# RF315.net
KiCad netlist of a schematic drawn in Altium Designer
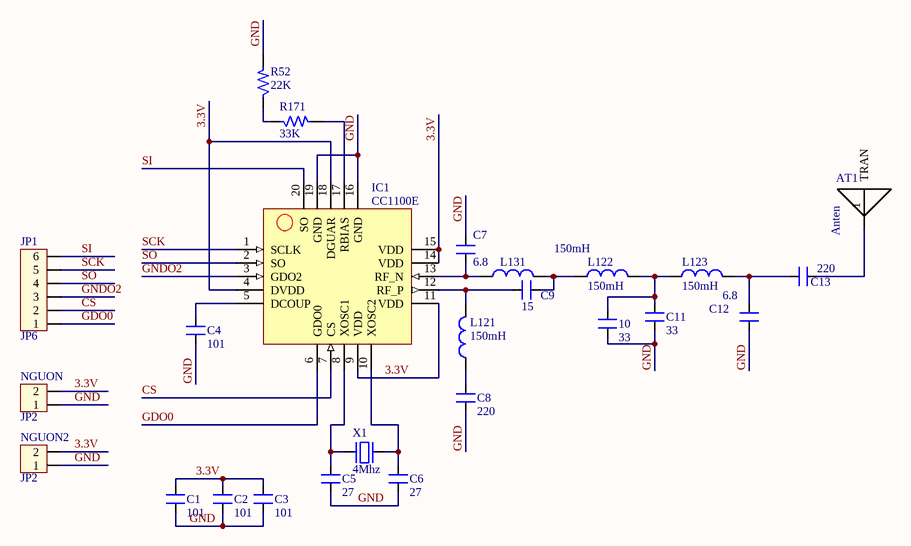
[diagram p0: RF315.SchDoc]

(export (version "E")
  (design (tool "Eeschema 10.0.6"))
  (components
    (comp (ref "10")
      (value "33")
      (footprint "SM-0805")
      (description "Cap SMD")
      (libsource (lib "syhaunguyen") (part "CM"))
    )
    (comp (ref "AT1") (value "Anten") (footprint "VIT") (libsource (lib "Antena") (part "Anten")))
    (comp (ref "C1")
      (value "101")
      (footprint "SM-0805")
      (description "Cap SMD")
      (libsource (lib "syhaunguyen") (part "CM"))
    )
    (comp (ref "C2")
      (value "101")
      (footprint "SM-0805")
      (description "Cap SMD")
      (libsource (lib "syhaunguyen") (part "CM"))
    )
    (comp (ref "C3")
      (value "101")
      (footprint "SM-0805")
      (description "Cap SMD")
      (libsource (lib "syhaunguyen") (part "CM"))
    )
    (comp (ref "C4")
      (value "101")
      (footprint "SM-0805")
      (description "Cap SMD")
      (libsource (lib "syhaunguyen") (part "CM"))
    )
    (comp (ref "C5")
      (value "27")
      (footprint "SM-0805")
      (description "Cap SMD")
      (libsource (lib "syhaunguyen") (part "CM"))
    )
    (comp (ref "C6")
      (value "27")
      (footprint "SM-0805")
      (description "Cap SMD")
      (libsource (lib "syhaunguyen") (part "CM"))
    )
    (comp (ref "C7")
      (value "6.8")
      (footprint "SM-0805")
      (description "Cap SMD")
      (libsource (lib "syhaunguyen") (part "CM"))
    )
    (comp (ref "C8")
      (value "220")
      (footprint "SM-0805")
      (description "Cap SMD")
      (libsource (lib "syhaunguyen") (part "CM"))
    )
    (comp (ref "C9")
      (value "15")
      (footprint "SM-0805")
      (description "Cap SMD")
      (libsource (lib "syhaunguyen") (part "CM"))
    )
    (comp (ref "C11")
      (value "33")
      (footprint "SM-0805")
      (description "Cap SMD")
      (libsource (lib "syhaunguyen") (part "CM"))
    )
    (comp (ref "C12")
      (value "6.8")
      (footprint "SM-0805")
      (description "Cap SMD")
      (libsource (lib "syhaunguyen") (part "CM"))
    )
    (comp (ref "C13")
      (value "220")
      (footprint "SM-0805")
      (description "Cap SMD")
      (libsource (lib "syhaunguyen") (part "CM"))
    )
    (comp (ref "IC1")
      (value "CC1100E")
      (footprint "PBL - SMD Packages:QFN50P500X500X80-33N")
      (libsource (lib "CC1100") (part "CC1100E"))
    )
    (comp (ref "JP1")
      (value "JP6")
      (footprint "CON6")
      (description "Connector 6")
      (libsource (lib "syhaunguyen") (part "Con6"))
    )
    (comp (ref "L121")
      (value "150mH")
      (footprint "L/0.4")
      (description "Inductor")
      (libsource (lib "syhaunguyen") (part "L1"))
    )
    (comp (ref "L122")
      (value "150mH")
      (footprint "L/0.4")
      (description "Inductor")
      (libsource (lib "syhaunguyen") (part "L1"))
    )
    (comp (ref "L123")
      (value "150mH")
      (footprint "L/0.4")
      (description "Inductor")
      (libsource (lib "syhaunguyen") (part "L1"))
    )
    (comp (ref "L131")
      (value "150mH")
      (footprint "L/0.4")
      (description "Inductor")
      (libsource (lib "syhaunguyen") (part "L1"))
    )
    (comp (ref "NGUON")
      (value "JP2")
      (footprint "CON2")
      (description "Connector 2")
      (libsource (lib "syhaunguyen") (part "Con2"))
    )
    (comp (ref "NGUON2")
      (value "JP2")
      (footprint "CON2")
      (description "Connector 2")
      (libsource (lib "syhaunguyen") (part "Con2"))
    )
    (comp (ref "R52")
      (value "22K")
      (footprint "SM-1206")
      (description "Resistor 1/4W")
      (libsource (lib "syhaunguyen") (part "R"))
    )
    (comp (ref "R171")
      (value "33K")
      (footprint "SM-0805")
      (description "Resistor 1/4W")
      (libsource (lib "syhaunguyen") (part "R"))
    )
    (comp (ref "X1")
      (value "4Mhz")
      (footprint "CP1/2.5_SM")
      (description "Crystal For all Crystal 2pin.")
      (libsource (lib "syhaunguyen") (part "XT2"))
    )
  )
  (nets
    (net (code "1") (name "/3.3V") (class "Default")
      (node (ref "C1") (pin "1") (pinfunction "1_1") (pintype "passive"))
      (node (ref "C2") (pin "1") (pinfunction "1_1") (pintype "passive"))
      (node (ref "C3") (pin "1") (pinfunction "1_1") (pintype "passive"))
      (node (ref "IC1") (pin "11") (pinfunction "VDD_11") (pintype "power_in"))
      (node (ref "IC1") (pin "14") (pinfunction "VDD_14") (pintype "power_in"))
      (node (ref "IC1") (pin "15") (pinfunction "VDD_15") (pintype "power_in"))
      (node (ref "IC1") (pin "18") (pinfunction "DGUAR_18") (pintype "passive"))
      (node (ref "IC1") (pin "4") (pinfunction "DVDD_4") (pintype "power_in"))
      (node (ref "IC1") (pin "9") (pinfunction "VDD_9") (pintype "power_in"))
      (node (ref "NGUON") (pin "2") (pinfunction "2_2") (pintype "passive"))
      (node (ref "NGUON2") (pin "2") (pinfunction "2_2") (pintype "passive"))
    )
    (net (code "2") (name "/CS") (class "Default")
      (node (ref "IC1") (pin "7") (pinfunction "CS_7") (pintype "input"))
      (node (ref "JP1") (pin "2") (pinfunction "2_2") (pintype "passive"))
    )
    (net (code "3") (name "/GDO0") (class "Default")
      (node (ref "IC1") (pin "6") (pinfunction "GDO0_6") (pintype "passive"))
      (node (ref "JP1") (pin "1") (pinfunction "1_1") (pintype "passive"))
    )
    (net (code "4") (name "/GND") (class "Default")
      (node (ref "10") (pin "1") (pinfunction "1_1") (pintype "passive"))
      (node (ref "C1") (pin "2") (pinfunction "2_2") (pintype "passive"))
      (node (ref "C11") (pin "1") (pinfunction "1_1") (pintype "passive"))
      (node (ref "C12") (pin "1") (pinfunction "1_1") (pintype "passive"))
      (node (ref "C2") (pin "2") (pinfunction "2_2") (pintype "passive"))
      (node (ref "C3") (pin "2") (pinfunction "2_2") (pintype "passive"))
      (node (ref "C4") (pin "2") (pinfunction "2_2") (pintype "passive"))
      (node (ref "C5") (pin "2") (pinfunction "2_2") (pintype "passive"))
      (node (ref "C6") (pin "2") (pinfunction "2_2") (pintype "passive"))
      (node (ref "C7") (pin "2") (pinfunction "2_2") (pintype "passive"))
      (node (ref "C8") (pin "1") (pinfunction "1_1") (pintype "passive"))
      (node (ref "IC1") (pin "16") (pinfunction "GND_16") (pintype "power_in"))
      (node (ref "IC1") (pin "19") (pinfunction "GND_19") (pintype "power_in"))
      (node (ref "NGUON") (pin "1") (pinfunction "1_1") (pintype "passive"))
      (node (ref "NGUON2") (pin "1") (pinfunction "1_1") (pintype "passive"))
      (node (ref "R52") (pin "2") (pinfunction "2_2") (pintype "passive"))
    )
    (net (code "5") (name "/GNDO2") (class "Default")
      (node (ref "IC1") (pin "3") (pinfunction "GDO2_3") (pintype "input"))
      (node (ref "JP1") (pin "3") (pinfunction "3_3") (pintype "passive"))
    )
    (net (code "6") (name "/SCK") (class "Default")
      (node (ref "IC1") (pin "1") (pinfunction "SCLK_1") (pintype "input"))
      (node (ref "JP1") (pin "5") (pinfunction "5_5") (pintype "passive"))
    )
    (net (code "7") (name "/SI") (class "Default")
      (node (ref "IC1") (pin "20") (pinfunction "SO_20") (pintype "passive"))
      (node (ref "JP1") (pin "6") (pinfunction "6_6") (pintype "passive"))
    )
    (net (code "8") (name "/SO") (class "Default")
      (node (ref "IC1") (pin "2") (pinfunction "SO_2") (pintype "input"))
      (node (ref "JP1") (pin "4") (pinfunction "4_4") (pintype "passive"))
    )
    (net (code "9") (name "Net-(10-Pad2)") (class "Default")
      (node (ref "10") (pin "2") (pinfunction "2_2") (pintype "passive"))
      (node (ref "C11") (pin "2") (pinfunction "2_2") (pintype "passive"))
      (node (ref "L122") (pin "2") (pinfunction "2_2") (pintype "passive"))
      (node (ref "L123") (pin "1") (pinfunction "1_1") (pintype "passive"))
    )
    (net (code "10") (name "Net-(AT1-TRAN)") (class "Default")
      (node (ref "AT1") (pin "1") (pinfunction "TRAN_1") (pintype "passive"))
      (node (ref "C13") (pin "1") (pinfunction "1_1") (pintype "passive"))
    )
    (net (code "11") (name "Net-(C8-Pad2)") (class "Default")
      (node (ref "C8") (pin "2") (pinfunction "2_2") (pintype "passive"))
      (node (ref "L121") (pin "1") (pinfunction "1_1") (pintype "passive"))
    )
    (net (code "12") (name "Net-(C9-Pad2)") (class "Default")
      (node (ref "C9") (pin "2") (pinfunction "2_2") (pintype "passive"))
      (node (ref "L122") (pin "1") (pinfunction "1_1") (pintype "passive"))
      (node (ref "L131") (pin "2") (pinfunction "2_2") (pintype "passive"))
    )
    (net (code "13") (name "Net-(C12-Pad2)") (class "Default")
      (node (ref "C12") (pin "2") (pinfunction "2_2") (pintype "passive"))
      (node (ref "C13") (pin "2") (pinfunction "2_2") (pintype "passive"))
      (node (ref "L123") (pin "2") (pinfunction "2_2") (pintype "passive"))
    )
    (net (code "14") (name "Net-(IC1-DCOUP)") (class "Default")
      (node (ref "C4") (pin "1") (pinfunction "1_1") (pintype "passive"))
      (node (ref "IC1") (pin "5") (pinfunction "DCOUP_5") (pintype "passive"))
    )
    (net (code "15") (name "Net-(IC1-RBIAS)") (class "Default")
      (node (ref "IC1") (pin "17") (pinfunction "RBIAS_17") (pintype "passive"))
      (node (ref "R171") (pin "2") (pinfunction "2_2") (pintype "passive"))
    )
    (net (code "16") (name "Net-(IC1-RF_N)") (class "Default")
      (node (ref "C7") (pin "1") (pinfunction "1_1") (pintype "passive"))
      (node (ref "IC1") (pin "13") (pinfunction "RF_N_13") (pintype "input"))
      (node (ref "L131") (pin "1") (pinfunction "1_1") (pintype "passive"))
    )
    (net (code "17") (name "Net-(IC1-RF_P)") (class "Default")
      (node (ref "C9") (pin "1") (pinfunction "1_1") (pintype "passive"))
      (node (ref "IC1") (pin "12") (pinfunction "RF_P_12") (pintype "output"))
      (node (ref "L121") (pin "2") (pinfunction "2_2") (pintype "passive"))
    )
    (net (code "18") (name "Net-(IC1-XOSC1)") (class "Default")
      (node (ref "C5") (pin "1") (pinfunction "1_1") (pintype "passive"))
      (node (ref "IC1") (pin "8") (pinfunction "XOSC1_8") (pintype "passive"))
      (node (ref "X1") (pin "1") (pinfunction "1_1") (pintype "passive"))
    )
    (net (code "19") (name "Net-(IC1-XOSC2)") (class "Default")
      (node (ref "C6") (pin "1") (pinfunction "1_1") (pintype "passive"))
      (node (ref "IC1") (pin "10") (pinfunction "XOSC2_10") (pintype "passive"))
      (node (ref "X1") (pin "2") (pinfunction "2_2") (pintype "passive"))
    )
    (net (code "20") (name "Net-(R171-Pad1)") (class "Default")
      (node (ref "R171") (pin "1") (pinfunction "1_1") (pintype "passive"))
      (node (ref "R52") (pin "1") (pinfunction "1_1") (pintype "passive"))
    )
  )
)
